# Tecleator.net
KiCad netlist of a schematic drawn in EAGLE
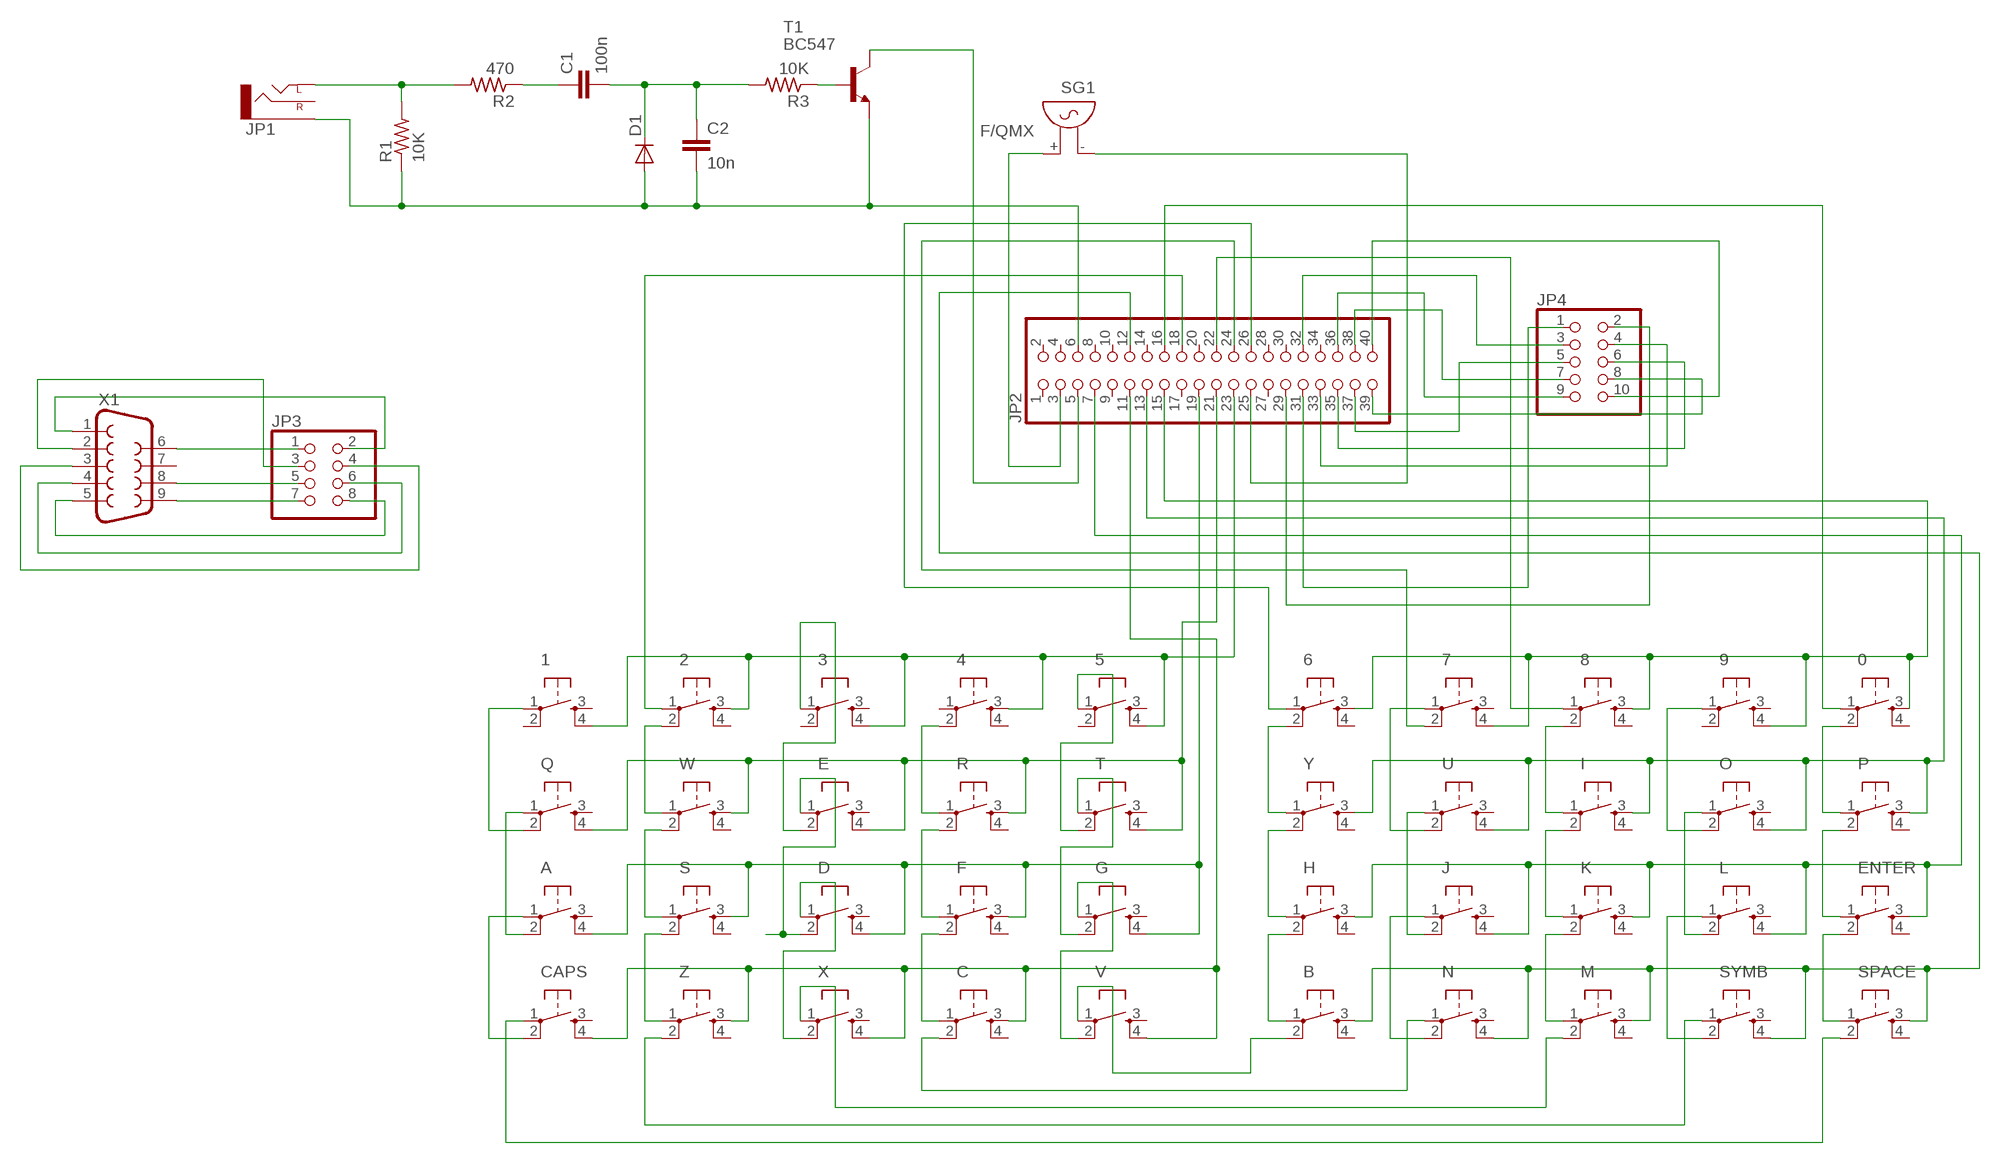
[diagram p0: schematic, sheet 1]

(export (version "E")
  (design (tool "Eeschema 10.0.6"))
  (components
    (comp (ref "0")
      (value "DTS-6")
      (footprint "eagle-import:DTS-6")
      (libsource (lib "eagle-import") (part "DTS-6"))
    )
    (comp (ref "1")
      (value "DTS-6")
      (footprint "eagle-import:DTS-6")
      (libsource (lib "eagle-import") (part "DTS-6"))
    )
    (comp (ref "2")
      (value "DTS-6")
      (footprint "eagle-import:DTS-6")
      (libsource (lib "eagle-import") (part "DTS-6"))
    )
    (comp (ref "3")
      (value "DTS-6")
      (footprint "eagle-import:DTS-6")
      (libsource (lib "eagle-import") (part "DTS-6"))
    )
    (comp (ref "4")
      (value "DTS-6")
      (footprint "eagle-import:DTS-6")
      (libsource (lib "eagle-import") (part "DTS-6"))
    )
    (comp (ref "5")
      (value "DTS-6")
      (footprint "eagle-import:DTS-6")
      (libsource (lib "eagle-import") (part "DTS-6"))
    )
    (comp (ref "6")
      (value "DTS-6")
      (footprint "eagle-import:DTS-6")
      (libsource (lib "eagle-import") (part "DTS-6"))
    )
    (comp (ref "7")
      (value "DTS-6")
      (footprint "eagle-import:DTS-6")
      (libsource (lib "eagle-import") (part "DTS-6"))
    )
    (comp (ref "8")
      (value "DTS-6")
      (footprint "eagle-import:DTS-6")
      (libsource (lib "eagle-import") (part "DTS-6"))
    )
    (comp (ref "9")
      (value "DTS-6")
      (footprint "eagle-import:DTS-6")
      (libsource (lib "eagle-import") (part "DTS-6"))
    )
    (comp (ref "A")
      (value "DTS-6")
      (footprint "eagle-import:DTS-6")
      (libsource (lib "eagle-import") (part "DTS-6"))
    )
    (comp (ref "B")
      (value "DTS-6")
      (footprint "eagle-import:DTS-6")
      (libsource (lib "eagle-import") (part "DTS-6"))
    )
    (comp (ref "C")
      (value "DTS-6")
      (footprint "eagle-import:DTS-6")
      (libsource (lib "eagle-import") (part "DTS-6"))
    )
    (comp (ref "C1")
      (value "100n")
      (footprint "eagle-import:C050-025X075")
      (libsource (lib "eagle-import") (part "C-EU050-025X075"))
    )
    (comp (ref "C2")
      (value "10n")
      (footprint "eagle-import:C050-025X075")
      (libsource (lib "eagle-import") (part "C-EU050-025X075"))
    )
    (comp (ref "CAPS")
      (value "DTS-6")
      (footprint "eagle-import:DTS-6")
      (libsource (lib "eagle-import") (part "DTS-6"))
    )
    (comp (ref "D")
      (value "DTS-6")
      (footprint "eagle-import:DTS-6")
      (libsource (lib "eagle-import") (part "DTS-6"))
    )
    (comp (ref "D1")
      (value "DIODE-DO41-7.6")
      (footprint "eagle-import:DO41-7.6")
      (libsource (lib "eagle-import") (part "DIODE-DO41-7.6"))
    )
    (comp (ref "E")
      (value "DTS-6")
      (footprint "eagle-import:DTS-6")
      (libsource (lib "eagle-import") (part "DTS-6"))
    )
    (comp (ref "ENTER")
      (value "DTS-6")
      (footprint "eagle-import:DTS-6")
      (libsource (lib "eagle-import") (part "DTS-6"))
    )
    (comp (ref "F")
      (value "DTS-6")
      (footprint "eagle-import:DTS-6")
      (libsource (lib "eagle-import") (part "DTS-6"))
    )
    (comp (ref "G")
      (value "DTS-6")
      (footprint "eagle-import:DTS-6")
      (libsource (lib "eagle-import") (part "DTS-6"))
    )
    (comp (ref "H")
      (value "DTS-6")
      (footprint "eagle-import:DTS-6")
      (libsource (lib "eagle-import") (part "DTS-6"))
    )
    (comp (ref "I")
      (value "DTS-6")
      (footprint "eagle-import:DTS-6")
      (libsource (lib "eagle-import") (part "DTS-6"))
    )
    (comp (ref "J")
      (value "DTS-6")
      (footprint "eagle-import:DTS-6")
      (libsource (lib "eagle-import") (part "DTS-6"))
    )
    (comp (ref "JP1")
      (value "AUDIO-JACKPTH")
      (footprint "eagle-import:AUDIO-JACK")
      (libsource (lib "eagle-import") (part "AUDIO-JACKPTH"))
    )
    (comp (ref "JP2")
      (value "PINHD-2X20")
      (footprint "eagle-import:2X20")
      (libsource (lib "eagle-import") (part "PINHD-2X20"))
    )
    (comp (ref "JP3")
      (value "PINHD-2X4")
      (footprint "eagle-import:2X04")
      (libsource (lib "eagle-import") (part "PINHD-2X4"))
    )
    (comp (ref "JP4")
      (value "PINHD-2X5")
      (footprint "eagle-import:2X05")
      (libsource (lib "eagle-import") (part "PINHD-2X5"))
    )
    (comp (ref "K")
      (value "DTS-6")
      (footprint "eagle-import:DTS-6")
      (libsource (lib "eagle-import") (part "DTS-6"))
    )
    (comp (ref "L")
      (value "DTS-6")
      (footprint "eagle-import:DTS-6")
      (libsource (lib "eagle-import") (part "DTS-6"))
    )
    (comp (ref "M")
      (value "DTS-6")
      (footprint "eagle-import:DTS-6")
      (libsource (lib "eagle-import") (part "DTS-6"))
    )
    (comp (ref "N")
      (value "DTS-6")
      (footprint "eagle-import:DTS-6")
      (libsource (lib "eagle-import") (part "DTS-6"))
    )
    (comp (ref "O")
      (value "DTS-6")
      (footprint "eagle-import:DTS-6")
      (libsource (lib "eagle-import") (part "DTS-6"))
    )
    (comp (ref "P")
      (value "DTS-6")
      (footprint "eagle-import:DTS-6")
      (libsource (lib "eagle-import") (part "DTS-6"))
    )
    (comp (ref "Q")
      (value "DTS-6")
      (footprint "eagle-import:DTS-6")
      (libsource (lib "eagle-import") (part "DTS-6"))
    )
    (comp (ref "R")
      (value "DTS-6")
      (footprint "eagle-import:DTS-6")
      (libsource (lib "eagle-import") (part "DTS-6"))
    )
    (comp (ref "R1")
      (value "10K")
      (footprint "eagle-import:0204_7")
      (libsource (lib "eagle-import") (part "R-US_0204/7"))
    )
    (comp (ref "R2")
      (value "470")
      (footprint "eagle-import:0204_7")
      (libsource (lib "eagle-import") (part "R-US_0204/7"))
    )
    (comp (ref "R3")
      (value "10K")
      (footprint "eagle-import:0204_7")
      (libsource (lib "eagle-import") (part "R-US_0204/7"))
    )
    (comp (ref "S")
      (value "DTS-6")
      (footprint "eagle-import:DTS-6")
      (libsource (lib "eagle-import") (part "DTS-6"))
    )
    (comp (ref "SG1")
      (value "F/QMX")
      (footprint "eagle-import:F_QMX")
      (libsource (lib "eagle-import") (part "F/QMX"))
    )
    (comp (ref "SPACE")
      (value "DTS-6")
      (footprint "eagle-import:DTS-6")
      (libsource (lib "eagle-import") (part "DTS-6"))
    )
    (comp (ref "SYMB")
      (value "DTS-6")
      (footprint "eagle-import:DTS-6")
      (libsource (lib "eagle-import") (part "DTS-6"))
    )
    (comp (ref "T")
      (value "DTS-6")
      (footprint "eagle-import:DTS-6")
      (libsource (lib "eagle-import") (part "DTS-6"))
    )
    (comp (ref "T1")
      (value "BC547")
      (footprint "eagle-import:TO92")
      (libsource (lib "eagle-import") (part "BC547"))
    )
    (comp (ref "U")
      (value "DTS-6")
      (footprint "eagle-import:DTS-6")
      (libsource (lib "eagle-import") (part "DTS-6"))
    )
    (comp (ref "V")
      (value "DTS-6")
      (footprint "eagle-import:DTS-6")
      (libsource (lib "eagle-import") (part "DTS-6"))
    )
    (comp (ref "W")
      (value "DTS-6")
      (footprint "eagle-import:DTS-6")
      (libsource (lib "eagle-import") (part "DTS-6"))
    )
    (comp (ref "X")
      (value "DTS-6")
      (footprint "eagle-import:DTS-6")
      (libsource (lib "eagle-import") (part "DTS-6"))
    )
    (comp (ref "X1")
      (value "DB9MALE")
      (footprint "eagle-import:DB9_MALE")
      (libsource (lib "eagle-import") (part "DB9MALE"))
    )
    (comp (ref "Y")
      (value "DTS-6")
      (footprint "eagle-import:DTS-6")
      (libsource (lib "eagle-import") (part "DTS-6"))
    )
    (comp (ref "Z")
      (value "DTS-6")
      (footprint "eagle-import:DTS-6")
      (libsource (lib "eagle-import") (part "DTS-6"))
    )
  )
  (nets
    (net (code "1") (name "Net-(0-Pad1)") (class "Default")
      (node (ref "0") (pin "1") (pinfunction "1_1") (pintype "passive"))
      (node (ref "JP2") (pin "16") (pinfunction "16_16") (pintype "passive"))
    )
    (net (code "2") (name "Net-(0-Pad2)") (class "Default")
      (node (ref "0") (pin "2") (pinfunction "2_2") (pintype "passive"))
      (node (ref "P") (pin "1") (pinfunction "1_1") (pintype "passive"))
    )
    (net (code "3") (name "Net-(0-Pad3)") (class "Default")
      (node (ref "0") (pin "3") (pinfunction "3_3") (pintype "passive"))
      (node (ref "6") (pin "3") (pinfunction "3_3") (pintype "passive"))
      (node (ref "7") (pin "4") (pinfunction "4_4") (pintype "passive"))
      (node (ref "8") (pin "3") (pinfunction "3_3") (pintype "passive"))
      (node (ref "9") (pin "4") (pinfunction "4_4") (pintype "passive"))
      (node (ref "JP2") (pin "15") (pinfunction "15_15") (pintype "passive"))
    )
    (net (code "4") (name "Net-(1-Pad1)") (class "Default")
      (node (ref "1") (pin "1") (pinfunction "1_1") (pintype "passive"))
      (node (ref "Q") (pin "2") (pinfunction "2_2") (pintype "passive"))
    )
    (net (code "5") (name "Net-(1-Pad4)") (class "Default")
      (node (ref "1") (pin "4") (pinfunction "4_4") (pintype "passive"))
      (node (ref "2") (pin "3") (pinfunction "3_3") (pintype "passive"))
      (node (ref "3") (pin "4") (pinfunction "4_4") (pintype "passive"))
      (node (ref "4") (pin "3") (pinfunction "3_3") (pintype "passive"))
      (node (ref "5") (pin "4") (pinfunction "4_4") (pintype "passive"))
      (node (ref "JP2") (pin "23") (pinfunction "23_23") (pintype "passive"))
    )
    (net (code "6") (name "Net-(2-Pad1)") (class "Default")
      (node (ref "2") (pin "1") (pinfunction "1_1") (pintype "passive"))
      (node (ref "JP2") (pin "18") (pinfunction "18_18") (pintype "passive"))
    )
    (net (code "7") (name "Net-(2-Pad2)") (class "Default")
      (node (ref "2") (pin "2") (pinfunction "2_2") (pintype "passive"))
      (node (ref "W") (pin "1") (pinfunction "1_1") (pintype "passive"))
    )
    (net (code "8") (name "Net-(3-Pad1)") (class "Default")
      (node (ref "3") (pin "1") (pinfunction "1_1") (pintype "passive"))
      (node (ref "E") (pin "2") (pinfunction "2_2") (pintype "passive"))
    )
    (net (code "9") (name "Net-(4-Pad2)") (class "Default")
      (node (ref "4") (pin "2") (pinfunction "2_2") (pintype "passive"))
      (node (ref "R") (pin "1") (pinfunction "1_1") (pintype "passive"))
    )
    (net (code "10") (name "Net-(5-Pad1)") (class "Default")
      (node (ref "5") (pin "1") (pinfunction "1_1") (pintype "passive"))
      (node (ref "T") (pin "2") (pinfunction "2_2") (pintype "passive"))
    )
    (net (code "11") (name "Net-(6-Pad1)") (class "Default")
      (node (ref "6") (pin "1") (pinfunction "1_1") (pintype "passive"))
      (node (ref "JP2") (pin "26") (pinfunction "26_26") (pintype "passive"))
    )
    (net (code "12") (name "Net-(6-Pad2)") (class "Default")
      (node (ref "6") (pin "2") (pinfunction "2_2") (pintype "passive"))
      (node (ref "Y") (pin "1") (pinfunction "1_1") (pintype "passive"))
    )
    (net (code "13") (name "Net-(7-Pad1)") (class "Default")
      (node (ref "7") (pin "1") (pinfunction "1_1") (pintype "passive"))
      (node (ref "U") (pin "2") (pinfunction "2_2") (pintype "passive"))
    )
    (net (code "14") (name "Net-(7-Pad2)") (class "Default")
      (node (ref "7") (pin "2") (pinfunction "2_2") (pintype "passive"))
      (node (ref "JP2") (pin "24") (pinfunction "24_24") (pintype "passive"))
    )
    (net (code "15") (name "Net-(8-Pad1)") (class "Default")
      (node (ref "8") (pin "1") (pinfunction "1_1") (pintype "passive"))
      (node (ref "JP2") (pin "22") (pinfunction "22_22") (pintype "passive"))
    )
    (net (code "16") (name "Net-(8-Pad2)") (class "Default")
      (node (ref "8") (pin "2") (pinfunction "2_2") (pintype "passive"))
      (node (ref "I") (pin "1") (pinfunction "1_1") (pintype "passive"))
    )
    (net (code "17") (name "Net-(9-Pad1)") (class "Default")
      (node (ref "9") (pin "1") (pinfunction "1_1") (pintype "passive"))
      (node (ref "O") (pin "2") (pinfunction "2_2") (pintype "passive"))
    )
    (net (code "18") (name "Net-(A-Pad1)") (class "Default")
      (node (ref "A") (pin "1") (pinfunction "1_1") (pintype "passive"))
      (node (ref "CAPS") (pin "2") (pinfunction "2_2") (pintype "passive"))
    )
    (net (code "19") (name "Net-(A-Pad2)") (class "Default")
      (node (ref "A") (pin "2") (pinfunction "2_2") (pintype "passive"))
      (node (ref "Q") (pin "1") (pinfunction "1_1") (pintype "passive"))
    )
    (net (code "20") (name "Net-(A-Pad4)") (class "Default")
      (node (ref "A") (pin "4") (pinfunction "4_4") (pintype "passive"))
      (node (ref "D") (pin "4") (pinfunction "4_4") (pintype "passive"))
      (node (ref "F") (pin "3") (pinfunction "3_3") (pintype "passive"))
      (node (ref "G") (pin "4") (pinfunction "4_4") (pintype "passive"))
      (node (ref "JP2") (pin "19") (pinfunction "19_19") (pintype "passive"))
      (node (ref "S") (pin "3") (pinfunction "3_3") (pintype "passive"))
    )
    (net (code "21") (name "Net-(B-Pad1)") (class "Default")
      (node (ref "B") (pin "1") (pinfunction "1_1") (pintype "passive"))
      (node (ref "H") (pin "2") (pinfunction "2_2") (pintype "passive"))
    )
    (net (code "22") (name "Net-(B-Pad2)") (class "Default")
      (node (ref "B") (pin "2") (pinfunction "2_2") (pintype "passive"))
      (node (ref "V") (pin "1") (pinfunction "1_1") (pintype "passive"))
    )
    (net (code "23") (name "Net-(B-Pad3)") (class "Default")
      (node (ref "B") (pin "3") (pinfunction "3_3") (pintype "passive"))
      (node (ref "JP2") (pin "12") (pinfunction "12_12") (pintype "passive"))
      (node (ref "M") (pin "3") (pinfunction "3_3") (pintype "passive"))
      (node (ref "N") (pin "4") (pinfunction "4_4") (pintype "passive"))
      (node (ref "SPACE") (pin "3") (pinfunction "3_3") (pintype "passive"))
      (node (ref "SYMB") (pin "4") (pinfunction "4_4") (pintype "passive"))
    )
    (net (code "24") (name "Net-(C-Pad1)") (class "Default")
      (node (ref "C") (pin "1") (pinfunction "1_1") (pintype "passive"))
      (node (ref "F") (pin "2") (pinfunction "2_2") (pintype "passive"))
    )
    (net (code "25") (name "Net-(C-Pad2)") (class "Default")
      (node (ref "C") (pin "2") (pinfunction "2_2") (pintype "passive"))
      (node (ref "N") (pin "1") (pinfunction "1_1") (pintype "passive"))
    )
    (net (code "26") (name "Net-(C-Pad3)") (class "Default")
      (node (ref "C") (pin "3") (pinfunction "3_3") (pintype "passive"))
      (node (ref "CAPS") (pin "4") (pinfunction "4_4") (pintype "passive"))
      (node (ref "JP2") (pin "11") (pinfunction "11_11") (pintype "passive"))
      (node (ref "V") (pin "4") (pinfunction "4_4") (pintype "passive"))
      (node (ref "X") (pin "4") (pinfunction "4_4") (pintype "passive"))
      (node (ref "Z") (pin "3") (pinfunction "3_3") (pintype "passive"))
    )
    (net (code "27") (name "Net-(C1-Pad1)") (class "Default")
      (node (ref "C1") (pin "1") (pinfunction "1_1") (pintype "passive"))
      (node (ref "R2") (pin "1") (pinfunction "1_1") (pintype "passive"))
    )
    (net (code "28") (name "Net-(C1-Pad2)") (class "Default")
      (node (ref "C1") (pin "2") (pinfunction "2_2") (pintype "passive"))
      (node (ref "C2") (pin "1") (pinfunction "1_1") (pintype "passive"))
      (node (ref "D1") (pin "C") (pinfunction "C_C") (pintype "passive"))
      (node (ref "R3") (pin "2") (pinfunction "2_2") (pintype "passive"))
    )
    (net (code "29") (name "Net-(CAPS-Pad1)") (class "Default")
      (node (ref "CAPS") (pin "1") (pinfunction "1_1") (pintype "passive"))
      (node (ref "SPACE") (pin "2") (pinfunction "2_2") (pintype "passive"))
    )
    (net (code "30") (name "Net-(D-Pad1)") (class "Default")
      (node (ref "D") (pin "1") (pinfunction "1_1") (pintype "passive"))
      (node (ref "X") (pin "2") (pinfunction "2_2") (pintype "passive"))
    )
    (net (code "31") (name "Net-(D-Pad2)") (class "Default")
      (node (ref "D") (pin "2") (pinfunction "2_2") (pintype "passive"))
      (node (ref "E") (pin "1") (pinfunction "1_1") (pintype "passive"))
    )
    (net (code "32") (name "Net-(E-Pad4)") (class "Default")
      (node (ref "E") (pin "4") (pinfunction "4_4") (pintype "passive"))
      (node (ref "JP2") (pin "21") (pinfunction "21_21") (pintype "passive"))
      (node (ref "Q") (pin "4") (pinfunction "4_4") (pintype "passive"))
      (node (ref "R") (pin "3") (pinfunction "3_3") (pintype "passive"))
      (node (ref "T") (pin "4") (pinfunction "4_4") (pintype "passive"))
      (node (ref "W") (pin "3") (pinfunction "3_3") (pintype "passive"))
    )
    (net (code "33") (name "Net-(ENTER-Pad1)") (class "Default")
      (node (ref "ENTER") (pin "1") (pinfunction "1_1") (pintype "passive"))
      (node (ref "P") (pin "2") (pinfunction "2_2") (pintype "passive"))
    )
    (net (code "34") (name "Net-(ENTER-Pad2)") (class "Default")
      (node (ref "ENTER") (pin "2") (pinfunction "2_2") (pintype "passive"))
      (node (ref "SPACE") (pin "1") (pinfunction "1_1") (pintype "passive"))
    )
    (net (code "35") (name "Net-(ENTER-Pad3)") (class "Default")
      (node (ref "ENTER") (pin "3") (pinfunction "3_3") (pintype "passive"))
      (node (ref "H") (pin "3") (pinfunction "3_3") (pintype "passive"))
      (node (ref "J") (pin "4") (pinfunction "4_4") (pintype "passive"))
      (node (ref "JP2") (pin "7") (pinfunction "7_7") (pintype "passive"))
      (node (ref "K") (pin "3") (pinfunction "3_3") (pintype "passive"))
      (node (ref "L") (pin "4") (pinfunction "4_4") (pintype "passive"))
    )
    (net (code "36") (name "Net-(F-Pad1)") (class "Default")
      (node (ref "F") (pin "1") (pinfunction "1_1") (pintype "passive"))
      (node (ref "R") (pin "2") (pinfunction "2_2") (pintype "passive"))
    )
    (net (code "37") (name "Net-(G-Pad1)") (class "Default")
      (node (ref "G") (pin "1") (pinfunction "1_1") (pintype "passive"))
      (node (ref "V") (pin "2") (pinfunction "2_2") (pintype "passive"))
    )
    (net (code "38") (name "Net-(G-Pad2)") (class "Default")
      (node (ref "G") (pin "2") (pinfunction "2_2") (pintype "passive"))
      (node (ref "T") (pin "1") (pinfunction "1_1") (pintype "passive"))
    )
    (net (code "39") (name "Net-(H-Pad1)") (class "Default")
      (node (ref "H") (pin "1") (pinfunction "1_1") (pintype "passive"))
      (node (ref "Y") (pin "2") (pinfunction "2_2") (pintype "passive"))
    )
    (net (code "40") (name "Net-(I-Pad2)") (class "Default")
      (node (ref "I") (pin "2") (pinfunction "2_2") (pintype "passive"))
      (node (ref "K") (pin "1") (pinfunction "1_1") (pintype "passive"))
    )
    (net (code "41") (name "Net-(I-Pad3)") (class "Default")
      (node (ref "I") (pin "3") (pinfunction "3_3") (pintype "passive"))
      (node (ref "JP2") (pin "13") (pinfunction "13_13") (pintype "passive"))
      (node (ref "O") (pin "4") (pinfunction "4_4") (pintype "passive"))
      (node (ref "P") (pin "3") (pinfunction "3_3") (pintype "passive"))
      (node (ref "U") (pin "4") (pinfunction "4_4") (pintype "passive"))
      (node (ref "Y") (pin "3") (pinfunction "3_3") (pintype "passive"))
    )
    (net (code "42") (name "Net-(J-Pad1)") (class "Default")
      (node (ref "J") (pin "1") (pinfunction "1_1") (pintype "passive"))
      (node (ref "N") (pin "2") (pinfunction "2_2") (pintype "passive"))
    )
    (net (code "43") (name "Net-(J-Pad2)") (class "Default")
      (node (ref "J") (pin "2") (pinfunction "2_2") (pintype "passive"))
      (node (ref "U") (pin "1") (pinfunction "1_1") (pintype "passive"))
    )
    (net (code "44") (name "Net-(JP1-LEFT)") (class "Default")
      (node (ref "JP1") (pin "TIP") (pinfunction "LEFT_TIP") (pintype "bidirectional"))
      (node (ref "R1") (pin "2") (pinfunction "2_2") (pintype "passive"))
      (node (ref "R2") (pin "2") (pinfunction "2_2") (pintype "passive"))
    )
    (net (code "45") (name "Net-(JP2-Pad29)") (class "Default")
      (node (ref "JP2") (pin "29") (pinfunction "29_29") (pintype "passive"))
      (node (ref "JP4") (pin "2") (pinfunction "2_2") (pintype "passive"))
    )
    (net (code "46") (name "Net-(JP2-Pad31)") (class "Default")
      (node (ref "JP2") (pin "31") (pinfunction "31_31") (pintype "passive"))
      (node (ref "JP4") (pin "1") (pinfunction "1_1") (pintype "passive"))
    )
    (net (code "47") (name "Net-(JP2-Pad32)") (class "Default")
      (node (ref "JP2") (pin "32") (pinfunction "32_32") (pintype "passive"))
      (node (ref "JP4") (pin "3") (pinfunction "3_3") (pintype "passive"))
    )
    (net (code "48") (name "Net-(JP2-Pad33)") (class "Default")
      (node (ref "JP2") (pin "33") (pinfunction "33_33") (pintype "passive"))
      (node (ref "JP4") (pin "4") (pinfunction "4_4") (pintype "passive"))
    )
    (net (code "49") (name "Net-(JP2-Pad35)") (class "Default")
      (node (ref "JP2") (pin "35") (pinfunction "35_35") (pintype "passive"))
      (node (ref "JP4") (pin "6") (pinfunction "6_6") (pintype "passive"))
    )
    (net (code "50") (name "Net-(JP2-Pad36)") (class "Default")
      (node (ref "JP2") (pin "36") (pinfunction "36_36") (pintype "passive"))
      (node (ref "JP4") (pin "9") (pinfunction "9_9") (pintype "passive"))
    )
    (net (code "51") (name "Net-(JP2-Pad37)") (class "Default")
      (node (ref "JP2") (pin "37") (pinfunction "37_37") (pintype "passive"))
      (node (ref "JP4") (pin "5") (pinfunction "5_5") (pintype "passive"))
    )
    (net (code "52") (name "Net-(JP2-Pad38)") (class "Default")
      (node (ref "JP2") (pin "38") (pinfunction "38_38") (pintype "passive"))
      (node (ref "JP4") (pin "7") (pinfunction "7_7") (pintype "passive"))
    )
    (net (code "53") (name "Net-(JP2-Pad39)") (class "Default")
      (node (ref "JP2") (pin "39") (pinfunction "39_39") (pintype "passive"))
      (node (ref "JP4") (pin "8") (pinfunction "8_8") (pintype "passive"))
    )
    (net (code "54") (name "Net-(JP2-Pad40)") (class "Default")
      (node (ref "JP2") (pin "40") (pinfunction "40_40") (pintype "passive"))
      (node (ref "JP4") (pin "10") (pinfunction "10_10") (pintype "passive"))
    )
    (net (code "55") (name "Net-(JP3-Pad1)") (class "Default")
      (node (ref "JP3") (pin "1") (pinfunction "1_1") (pintype "passive"))
      (node (ref "X1") (pin "6") (pinfunction "6_6") (pintype "passive"))
    )
    (net (code "56") (name "Net-(JP3-Pad2)") (class "Default")
      (node (ref "JP3") (pin "2") (pinfunction "2_2") (pintype "passive"))
      (node (ref "X1") (pin "1") (pinfunction "1_1") (pintype "passive"))
    )
    (net (code "57") (name "Net-(JP3-Pad3)") (class "Default")
      (node (ref "JP3") (pin "3") (pinfunction "3_3") (pintype "passive"))
      (node (ref "X1") (pin "2") (pinfunction "2_2") (pintype "passive"))
    )
    (net (code "58") (name "Net-(JP3-Pad4)") (class "Default")
      (node (ref "JP3") (pin "4") (pinfunction "4_4") (pintype "passive"))
      (node (ref "X1") (pin "3") (pinfunction "3_3") (pintype "passive"))
    )
    (net (code "59") (name "Net-(JP3-Pad5)") (class "Default")
      (node (ref "JP3") (pin "5") (pinfunction "5_5") (pintype "passive"))
      (node (ref "X1") (pin "8") (pinfunction "8_8") (pintype "passive"))
    )
    (net (code "60") (name "Net-(JP3-Pad6)") (class "Default")
      (node (ref "JP3") (pin "6") (pinfunction "6_6") (pintype "passive"))
      (node (ref "X1") (pin "4") (pinfunction "4_4") (pintype "passive"))
    )
    (net (code "61") (name "Net-(JP3-Pad7)") (class "Default")
      (node (ref "JP3") (pin "7") (pinfunction "7_7") (pintype "passive"))
      (node (ref "X1") (pin "9") (pinfunction "9_9") (pintype "passive"))
    )
    (net (code "62") (name "Net-(JP3-Pad8)") (class "Default")
      (node (ref "JP3") (pin "8") (pinfunction "8_8") (pintype "passive"))
      (node (ref "X1") (pin "5") (pinfunction "5_5") (pintype "passive"))
    )
    (net (code "63") (name "Net-(K-Pad2)") (class "Default")
      (node (ref "K") (pin "2") (pinfunction "2_2") (pintype "passive"))
      (node (ref "M") (pin "1") (pinfunction "1_1") (pintype "passive"))
    )
    (net (code "64") (name "Net-(L-Pad1)") (class "Default")
      (node (ref "L") (pin "1") (pinfunction "1_1") (pintype "passive"))
      (node (ref "SYMB") (pin "2") (pinfunction "2_2") (pintype "passive"))
    )
    (net (code "65") (name "Net-(L-Pad2)") (class "Default")
      (node (ref "L") (pin "2") (pinfunction "2_2") (pintype "passive"))
      (node (ref "O") (pin "1") (pinfunction "1_1") (pintype "passive"))
    )
    (net (code "66") (name "Net-(M-Pad2)") (class "Default")
      (node (ref "M") (pin "2") (pinfunction "2_2") (pintype "passive"))
      (node (ref "X") (pin "1") (pinfunction "1_1") (pintype "passive"))
    )
    (net (code "67") (name "Net-(S-Pad1)") (class "Default")
      (node (ref "S") (pin "1") (pinfunction "1_1") (pintype "passive"))
      (node (ref "W") (pin "2") (pinfunction "2_2") (pintype "passive"))
    )
    (net (code "68") (name "Net-(S-Pad2)") (class "Default")
      (node (ref "S") (pin "2") (pinfunction "2_2") (pintype "passive"))
      (node (ref "Z") (pin "1") (pinfunction "1_1") (pintype "passive"))
    )
    (net (code "69") (name "Net-(SG1-1)") (class "Default")
      (node (ref "JP2") (pin "25") (pinfunction "25_25") (pintype "passive"))
      (node (ref "SG1") (pin "-") (pinfunction "1_-") (pintype "passive"))
    )
    (net (code "70") (name "Net-(SG1-2)") (class "Default")
      (node (ref "JP2") (pin "3") (pinfunction "3_3") (pintype "passive"))
      (node (ref "SG1") (pin "+") (pinfunction "2_+") (pintype "passive"))
    )
    (net (code "71") (name "Net-(SYMB-Pad1)") (class "Default")
      (node (ref "SYMB") (pin "1") (pinfunction "1_1") (pintype "passive"))
      (node (ref "Z") (pin "2") (pinfunction "2_2") (pintype "passive"))
    )
    (net (code "72") (name "Net-(T1-B)") (class "Default")
      (node (ref "R3") (pin "1") (pinfunction "1_1") (pintype "passive"))
      (node (ref "T1") (pin "2") (pinfunction "B_2") (pintype "passive"))
    )
    (net (code "73") (name "Net-(T1-C)") (class "Default")
      (node (ref "JP2") (pin "5") (pinfunction "5_5") (pintype "passive"))
      (node (ref "T1") (pin "3") (pinfunction "C_3") (pintype "passive"))
    )
    (net (code "74") (name "Net-(T1-E)") (class "Default")
      (node (ref "C2") (pin "2") (pinfunction "2_2") (pintype "passive"))
      (node (ref "D1") (pin "A") (pinfunction "A_A") (pintype "passive"))
      (node (ref "JP1") (pin "SLEEVE") (pinfunction "SLEEVE_SLEEVE") (pintype "bidirectional"))
      (node (ref "JP2") (pin "6") (pinfunction "6_6") (pintype "passive"))
      (node (ref "R1") (pin "1") (pinfunction "1_1") (pintype "passive"))
      (node (ref "T1") (pin "1") (pinfunction "E_1") (pintype "passive"))
    )
    (net (code "75") (name "unconnected-(0-Pad4)") (class "Default")
      (node (ref "0") (pin "4") (pinfunction "4_4") (pintype "passive"))
    )
    (net (code "76") (name "unconnected-(1-Pad2)") (class "Default")
      (node (ref "1") (pin "2") (pinfunction "2_2") (pintype "passive"))
    )
    (net (code "77") (name "unconnected-(1-Pad3)") (class "Default")
      (node (ref "1") (pin "3") (pinfunction "3_3") (pintype "passive"))
    )
    (net (code "78") (name "unconnected-(2-Pad4)") (class "Default")
      (node (ref "2") (pin "4") (pinfunction "4_4") (pintype "passive"))
    )
    (net (code "79") (name "unconnected-(3-Pad2)") (class "Default")
      (node (ref "3") (pin "2") (pinfunction "2_2") (pintype "passive"))
    )
    (net (code "80") (name "unconnected-(3-Pad3)") (class "Default")
      (node (ref "3") (pin "3") (pinfunction "3_3") (pintype "passive"))
    )
    (net (code "81") (name "unconnected-(4-Pad1)") (class "Default")
      (node (ref "4") (pin "1") (pinfunction "1_1") (pintype "passive"))
    )
    (net (code "82") (name "unconnected-(4-Pad4)") (class "Default")
      (node (ref "4") (pin "4") (pinfunction "4_4") (pintype "passive"))
    )
    (net (code "83") (name "unconnected-(5-Pad2)") (class "Default")
      (node (ref "5") (pin "2") (pinfunction "2_2") (pintype "passive"))
    )
    (net (code "84") (name "unconnected-(5-Pad3)") (class "Default")
      (node (ref "5") (pin "3") (pinfunction "3_3") (pintype "passive"))
    )
    (net (code "85") (name "unconnected-(6-Pad4)") (class "Default")
      (node (ref "6") (pin "4") (pinfunction "4_4") (pintype "passive"))
    )
    (net (code "86") (name "unconnected-(7-Pad3)") (class "Default")
      (node (ref "7") (pin "3") (pinfunction "3_3") (pintype "passive"))
    )
    (net (code "87") (name "unconnected-(8-Pad4)") (class "Default")
      (node (ref "8") (pin "4") (pinfunction "4_4") (pintype "passive"))
    )
    (net (code "88") (name "unconnected-(9-Pad2)") (class "Default")
      (node (ref "9") (pin "2") (pinfunction "2_2") (pintype "passive"))
    )
    (net (code "89") (name "unconnected-(9-Pad3)") (class "Default")
      (node (ref "9") (pin "3") (pinfunction "3_3") (pintype "passive"))
    )
    (net (code "90") (name "unconnected-(A-Pad3)") (class "Default")
      (node (ref "A") (pin "3") (pinfunction "3_3") (pintype "passive"))
    )
    (net (code "91") (name "unconnected-(B-Pad4)") (class "Default")
      (node (ref "B") (pin "4") (pinfunction "4_4") (pintype "passive"))
    )
    (net (code "92") (name "unconnected-(C-Pad4)") (class "Default")
      (node (ref "C") (pin "4") (pinfunction "4_4") (pintype "passive"))
    )
    (net (code "93") (name "unconnected-(CAPS-Pad3)") (class "Default")
      (node (ref "CAPS") (pin "3") (pinfunction "3_3") (pintype "passive"))
    )
    (net (code "94") (name "unconnected-(D-Pad3)") (class "Default")
      (node (ref "D") (pin "3") (pinfunction "3_3") (pintype "passive"))
    )
    (net (code "95") (name "unconnected-(E-Pad3)") (class "Default")
      (node (ref "E") (pin "3") (pinfunction "3_3") (pintype "passive"))
    )
    (net (code "96") (name "unconnected-(ENTER-Pad4)") (class "Default")
      (node (ref "ENTER") (pin "4") (pinfunction "4_4") (pintype "passive"))
    )
    (net (code "97") (name "unconnected-(F-Pad4)") (class "Default")
      (node (ref "F") (pin "4") (pinfunction "4_4") (pintype "passive"))
    )
    (net (code "98") (name "unconnected-(G-Pad3)") (class "Default")
      (node (ref "G") (pin "3") (pinfunction "3_3") (pintype "passive"))
    )
    (net (code "99") (name "unconnected-(H-Pad4)") (class "Default")
      (node (ref "H") (pin "4") (pinfunction "4_4") (pintype "passive"))
    )
    (net (code "100") (name "unconnected-(I-Pad4)") (class "Default")
      (node (ref "I") (pin "4") (pinfunction "4_4") (pintype "passive"))
    )
    (net (code "101") (name "unconnected-(J-Pad3)") (class "Default")
      (node (ref "J") (pin "3") (pinfunction "3_3") (pintype "passive"))
    )
    (net (code "102") (name "unconnected-(JP1-RIGHT-PadRING)") (class "Default")
      (node (ref "JP1") (pin "RING") (pinfunction "RIGHT_RING") (pintype "bidirectional"))
    )
    (net (code "103") (name "unconnected-(JP2-Pad1)") (class "Default")
      (node (ref "JP2") (pin "1") (pinfunction "1_1") (pintype "passive"))
    )
    (net (code "104") (name "unconnected-(JP2-Pad2)") (class "Default")
      (node (ref "JP2") (pin "2") (pinfunction "2_2") (pintype "passive"))
    )
    (net (code "105") (name "unconnected-(JP2-Pad4)") (class "Default")
      (node (ref "JP2") (pin "4") (pinfunction "4_4") (pintype "passive"))
    )
    (net (code "106") (name "unconnected-(JP2-Pad8)") (class "Default")
      (node (ref "JP2") (pin "8") (pinfunction "8_8") (pintype "passive"))
    )
    (net (code "107") (name "unconnected-(JP2-Pad9)") (class "Default")
      (node (ref "JP2") (pin "9") (pinfunction "9_9") (pintype "passive"))
    )
    (net (code "108") (name "unconnected-(JP2-Pad10)") (class "Default")
      (node (ref "JP2") (pin "10") (pinfunction "10_10") (pintype "passive"))
    )
    (net (code "109") (name "unconnected-(JP2-Pad14)") (class "Default")
      (node (ref "JP2") (pin "14") (pinfunction "14_14") (pintype "passive"))
    )
    (net (code "110") (name "unconnected-(JP2-Pad17)") (class "Default")
      (node (ref "JP2") (pin "17") (pinfunction "17_17") (pintype "passive"))
    )
    (net (code "111") (name "unconnected-(JP2-Pad20)") (class "Default")
      (node (ref "JP2") (pin "20") (pinfunction "20_20") (pintype "passive"))
    )
    (net (code "112") (name "unconnected-(JP2-Pad27)") (class "Default")
      (node (ref "JP2") (pin "27") (pinfunction "27_27") (pintype "passive"))
    )
    (net (code "113") (name "unconnected-(JP2-Pad28)") (class "Default")
      (node (ref "JP2") (pin "28") (pinfunction "28_28") (pintype "passive"))
    )
    (net (code "114") (name "unconnected-(JP2-Pad30)") (class "Default")
      (node (ref "JP2") (pin "30") (pinfunction "30_30") (pintype "passive"))
    )
    (net (code "115") (name "unconnected-(JP2-Pad34)") (class "Default")
      (node (ref "JP2") (pin "34") (pinfunction "34_34") (pintype "passive"))
    )
    (net (code "116") (name "unconnected-(K-Pad4)") (class "Default")
      (node (ref "K") (pin "4") (pinfunction "4_4") (pintype "passive"))
    )
    (net (code "117") (name "unconnected-(L-Pad3)") (class "Default")
      (node (ref "L") (pin "3") (pinfunction "3_3") (pintype "passive"))
    )
    (net (code "118") (name "unconnected-(M-Pad4)") (class "Default")
      (node (ref "M") (pin "4") (pinfunction "4_4") (pintype "passive"))
    )
    (net (code "119") (name "unconnected-(N-Pad3)") (class "Default")
      (node (ref "N") (pin "3") (pinfunction "3_3") (pintype "passive"))
    )
    (net (code "120") (name "unconnected-(O-Pad3)") (class "Default")
      (node (ref "O") (pin "3") (pinfunction "3_3") (pintype "passive"))
    )
    (net (code "121") (name "unconnected-(P-Pad4)") (class "Default")
      (node (ref "P") (pin "4") (pinfunction "4_4") (pintype "passive"))
    )
    (net (code "122") (name "unconnected-(Q-Pad3)") (class "Default")
      (node (ref "Q") (pin "3") (pinfunction "3_3") (pintype "passive"))
    )
    (net (code "123") (name "unconnected-(R-Pad4)") (class "Default")
      (node (ref "R") (pin "4") (pinfunction "4_4") (pintype "passive"))
    )
    (net (code "124") (name "unconnected-(S-Pad4)") (class "Default")
      (node (ref "S") (pin "4") (pinfunction "4_4") (pintype "passive"))
    )
    (net (code "125") (name "unconnected-(SPACE-Pad4)") (class "Default")
      (node (ref "SPACE") (pin "4") (pinfunction "4_4") (pintype "passive"))
    )
    (net (code "126") (name "unconnected-(SYMB-Pad3)") (class "Default")
      (node (ref "SYMB") (pin "3") (pinfunction "3_3") (pintype "passive"))
    )
    (net (code "127") (name "unconnected-(T-Pad3)") (class "Default")
      (node (ref "T") (pin "3") (pinfunction "3_3") (pintype "passive"))
    )
    (net (code "128") (name "unconnected-(U-Pad3)") (class "Default")
      (node (ref "U") (pin "3") (pinfunction "3_3") (pintype "passive"))
    )
    (net (code "129") (name "unconnected-(V-Pad3)") (class "Default")
      (node (ref "V") (pin "3") (pinfunction "3_3") (pintype "passive"))
    )
    (net (code "130") (name "unconnected-(W-Pad4)") (class "Default")
      (node (ref "W") (pin "4") (pinfunction "4_4") (pintype "passive"))
    )
    (net (code "131") (name "unconnected-(X-Pad3)") (class "Default")
      (node (ref "X") (pin "3") (pinfunction "3_3") (pintype "passive"))
    )
    (net (code "132") (name "unconnected-(X1-Pad7)") (class "Default")
      (node (ref "X1") (pin "7") (pinfunction "7_7") (pintype "passive"))
    )
    (net (code "133") (name "unconnected-(Y-Pad4)") (class "Default")
      (node (ref "Y") (pin "4") (pinfunction "4_4") (pintype "passive"))
    )
    (net (code "134") (name "unconnected-(Z-Pad4)") (class "Default")
      (node (ref "Z") (pin "4") (pinfunction "4_4") (pintype "passive"))
    )
  )
)
